# iF11L.net
KiCad netlist of a schematic drawn in Altium Designer
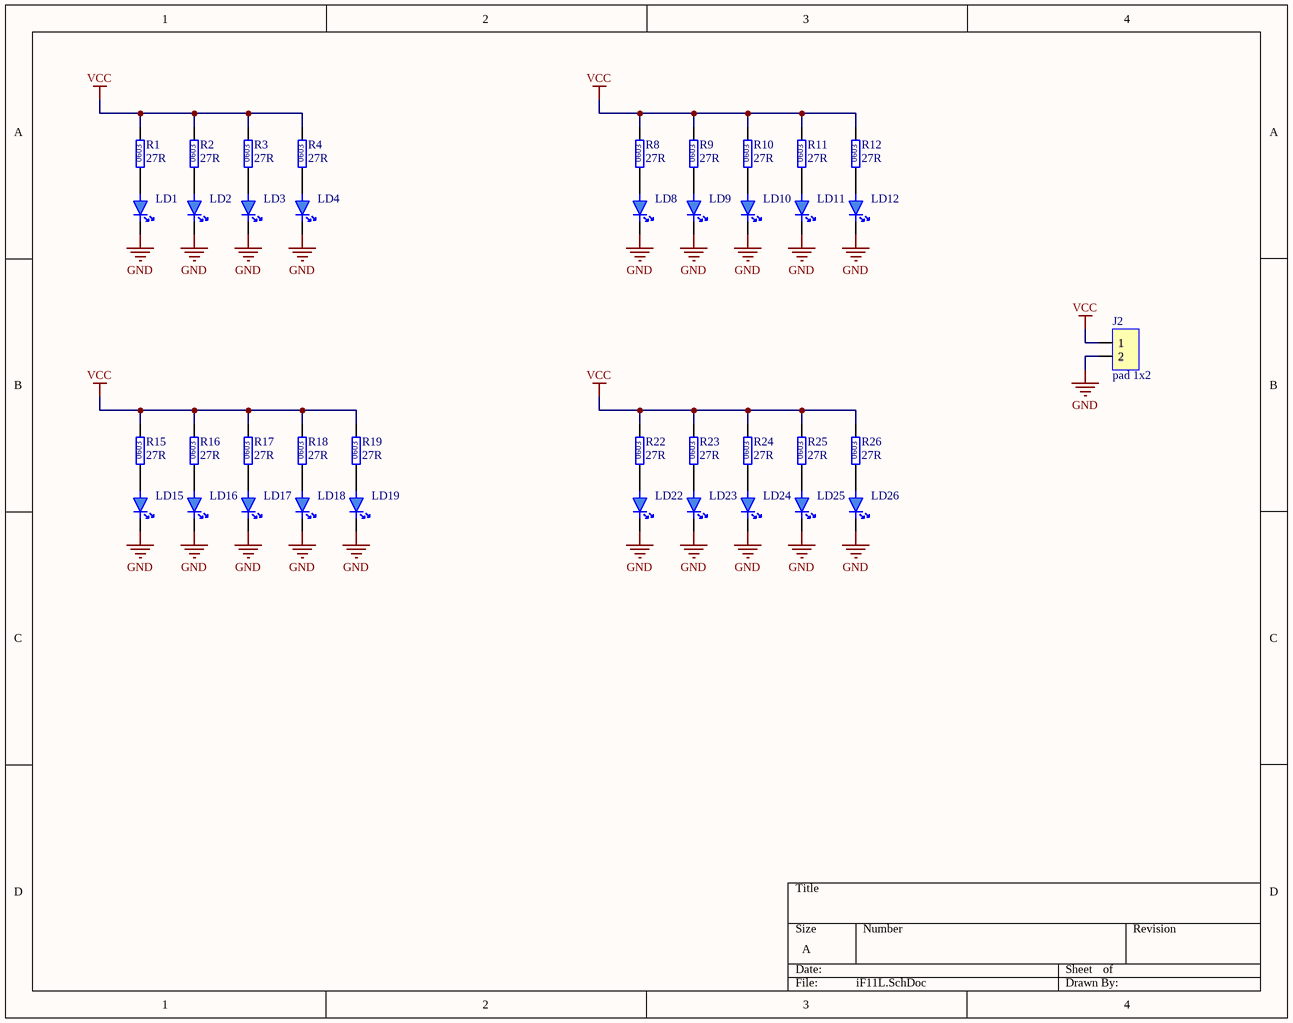
[diagram p0: iF11L.SchDoc]

(export (version "E")
  (design (tool "Eeschema 10.0.6"))
  (components
    (comp (ref "J2")
      (value "pad 1x2")
      (footprint "Pad-1x2")
      (description "2 Pin SMD Pad")
      (libsource (lib "Connector") (part "Pad-1x2"))
    )
    (comp (ref "LD1")
      (value "HQ19-2101UWCE2 0603")
      (footprint "LED-0603-WS")
      (libsource (lib "Optoelectronics") (part "LED WS"))
    )
    (comp (ref "LD2")
      (value "HQ19-2101UWCE2 0603")
      (footprint "LED-0603-WS")
      (libsource (lib "Optoelectronics") (part "LED WS"))
    )
    (comp (ref "LD3")
      (value "HQ19-2101UWCE2 0603")
      (footprint "LED-0603-WS")
      (libsource (lib "Optoelectronics") (part "LED WS"))
    )
    (comp (ref "LD4")
      (value "HQ19-2101UWCE2 0603")
      (footprint "LED-0603-WS")
      (libsource (lib "Optoelectronics") (part "LED WS"))
    )
    (comp (ref "LD8")
      (value "HQ19-2101UWCE2 0603")
      (footprint "LED-0603-WS")
      (libsource (lib "Optoelectronics") (part "LED WS"))
    )
    (comp (ref "LD9")
      (value "HQ19-2101UWCE2 0603")
      (footprint "LED-0603-WS")
      (libsource (lib "Optoelectronics") (part "LED WS"))
    )
    (comp (ref "LD10")
      (value "HQ19-2101UWCE2 0603")
      (footprint "LED-0603-WS")
      (libsource (lib "Optoelectronics") (part "LED WS"))
    )
    (comp (ref "LD11")
      (value "HQ19-2101UWCE2 0603")
      (footprint "LED-0603-WS")
      (libsource (lib "Optoelectronics") (part "LED WS"))
    )
    (comp (ref "LD12")
      (value "HQ19-2101UWCE2 0603")
      (footprint "LED-0603-WS")
      (libsource (lib "Optoelectronics") (part "LED WS"))
    )
    (comp (ref "LD15")
      (value "HQ19-2101UWCE2 0603")
      (footprint "LED-0603-WS")
      (libsource (lib "Optoelectronics") (part "LED WS"))
    )
    (comp (ref "LD16")
      (value "HQ19-2101UWCE2 0603")
      (footprint "LED-0603-WS")
      (libsource (lib "Optoelectronics") (part "LED WS"))
    )
    (comp (ref "LD17")
      (value "HQ19-2101UWCE2 0603")
      (footprint "LED-0603-WS")
      (libsource (lib "Optoelectronics") (part "LED WS"))
    )
    (comp (ref "LD18")
      (value "HQ19-2101UWCE2 0603")
      (footprint "LED-0603-WS")
      (libsource (lib "Optoelectronics") (part "LED WS"))
    )
    (comp (ref "LD19")
      (value "HQ19-2101UWCE2 0603")
      (footprint "LED-0603-WS")
      (libsource (lib "Optoelectronics") (part "LED WS"))
    )
    (comp (ref "LD22")
      (value "HQ19-2101UWCE2 0603")
      (footprint "LED-0603-WS")
      (libsource (lib "Optoelectronics") (part "LED WS"))
    )
    (comp (ref "LD23")
      (value "HQ19-2101UWCE2 0603")
      (footprint "LED-0603-WS")
      (libsource (lib "Optoelectronics") (part "LED WS"))
    )
    (comp (ref "LD24")
      (value "HQ19-2101UWCE2 0603")
      (footprint "LED-0603-WS")
      (libsource (lib "Optoelectronics") (part "LED WS"))
    )
    (comp (ref "LD25")
      (value "HQ19-2101UWCE2 0603")
      (footprint "LED-0603-WS")
      (libsource (lib "Optoelectronics") (part "LED WS"))
    )
    (comp (ref "LD26")
      (value "HQ19-2101UWCE2 0603")
      (footprint "LED-0603-WS")
      (libsource (lib "Optoelectronics") (part "LED WS"))
    )
    (comp (ref "R1")
      (value "27R")
      (footprint "R0603-LD")
      (description "5%")
      (fields (field (name "PART NO") "W-T-RE-RS03K270JT") (field (name "MANUFACTURER") "LAGEO"))
      (libsource (lib "Rescap") (part "R 0603 27R"))
    )
    (comp (ref "R2")
      (value "27R")
      (footprint "R0603-LD")
      (description "5%")
      (fields (field (name "PART NO") "W-T-RE-RS03K270JT") (field (name "MANUFACTURER") "LAGEO"))
      (libsource (lib "Rescap") (part "R 0603 27R"))
    )
    (comp (ref "R3")
      (value "27R")
      (footprint "R0603-LD")
      (description "5%")
      (fields (field (name "PART NO") "W-T-RE-RS03K270JT") (field (name "MANUFACTURER") "LAGEO"))
      (libsource (lib "Rescap") (part "R 0603 27R"))
    )
    (comp (ref "R4")
      (value "27R")
      (footprint "R0603-LD")
      (description "5%")
      (fields (field (name "PART NO") "W-T-RE-RS03K270JT") (field (name "MANUFACTURER") "LAGEO"))
      (libsource (lib "Rescap") (part "R 0603 27R"))
    )
    (comp (ref "R8")
      (value "27R")
      (footprint "R0603-LD")
      (description "5%")
      (fields (field (name "PART NO") "W-T-RE-RS03K270JT") (field (name "MANUFACTURER") "LAGEO"))
      (libsource (lib "Rescap") (part "R 0603 27R"))
    )
    (comp (ref "R9")
      (value "27R")
      (footprint "R0603-LD")
      (description "5%")
      (fields (field (name "PART NO") "W-T-RE-RS03K270JT") (field (name "MANUFACTURER") "LAGEO"))
      (libsource (lib "Rescap") (part "R 0603 27R"))
    )
    (comp (ref "R10")
      (value "27R")
      (footprint "R0603-LD")
      (description "5%")
      (fields (field (name "PART NO") "W-T-RE-RS03K270JT") (field (name "MANUFACTURER") "LAGEO"))
      (libsource (lib "Rescap") (part "R 0603 27R"))
    )
    (comp (ref "R11")
      (value "27R")
      (footprint "R0603-LD")
      (description "5%")
      (fields (field (name "PART NO") "W-T-RE-RS03K270JT") (field (name "MANUFACTURER") "LAGEO"))
      (libsource (lib "Rescap") (part "R 0603 27R"))
    )
    (comp (ref "R12")
      (value "27R")
      (footprint "R0603-LD")
      (description "5%")
      (fields (field (name "PART NO") "W-T-RE-RS03K270JT") (field (name "MANUFACTURER") "LAGEO"))
      (libsource (lib "Rescap") (part "R 0603 27R"))
    )
    (comp (ref "R15")
      (value "27R")
      (footprint "R0603-LD")
      (description "5%")
      (fields (field (name "PART NO") "W-T-RE-RS03K270JT") (field (name "MANUFACTURER") "LAGEO"))
      (libsource (lib "Rescap") (part "R 0603 27R"))
    )
    (comp (ref "R16")
      (value "27R")
      (footprint "R0603-LD")
      (description "5%")
      (fields (field (name "PART NO") "W-T-RE-RS03K270JT") (field (name "MANUFACTURER") "LAGEO"))
      (libsource (lib "Rescap") (part "R 0603 27R"))
    )
    (comp (ref "R17")
      (value "27R")
      (footprint "R0603-LD")
      (description "5%")
      (fields (field (name "PART NO") "W-T-RE-RS03K270JT") (field (name "MANUFACTURER") "LAGEO"))
      (libsource (lib "Rescap") (part "R 0603 27R"))
    )
    (comp (ref "R18")
      (value "27R")
      (footprint "R0603-LD")
      (description "5%")
      (fields (field (name "PART NO") "W-T-RE-RS03K270JT") (field (name "MANUFACTURER") "LAGEO"))
      (libsource (lib "Rescap") (part "R 0603 27R"))
    )
    (comp (ref "R19")
      (value "27R")
      (footprint "R0603-LD")
      (description "5%")
      (fields (field (name "PART NO") "W-T-RE-RS03K270JT") (field (name "MANUFACTURER") "LAGEO"))
      (libsource (lib "Rescap") (part "R 0603 27R"))
    )
    (comp (ref "R22")
      (value "27R")
      (footprint "R0603-LD")
      (description "5%")
      (fields (field (name "PART NO") "W-T-RE-RS03K270JT") (field (name "MANUFACTURER") "LAGEO"))
      (libsource (lib "Rescap") (part "R 0603 27R"))
    )
    (comp (ref "R23")
      (value "27R")
      (footprint "R0603-LD")
      (description "5%")
      (fields (field (name "PART NO") "W-T-RE-RS03K270JT") (field (name "MANUFACTURER") "LAGEO"))
      (libsource (lib "Rescap") (part "R 0603 27R"))
    )
    (comp (ref "R24")
      (value "27R")
      (footprint "R0603-LD")
      (description "5%")
      (fields (field (name "PART NO") "W-T-RE-RS03K270JT") (field (name "MANUFACTURER") "LAGEO"))
      (libsource (lib "Rescap") (part "R 0603 27R"))
    )
    (comp (ref "R25")
      (value "27R")
      (footprint "R0603-LD")
      (description "5%")
      (fields (field (name "PART NO") "W-T-RE-RS03K270JT") (field (name "MANUFACTURER") "LAGEO"))
      (libsource (lib "Rescap") (part "R 0603 27R"))
    )
    (comp (ref "R26")
      (value "27R")
      (footprint "R0603-LD")
      (description "5%")
      (fields (field (name "PART NO") "W-T-RE-RS03K270JT") (field (name "MANUFACTURER") "LAGEO"))
      (libsource (lib "Rescap") (part "R 0603 27R"))
    )
  )
  (nets
    (net (code "1") (name "GND") (class "Default")
      (node (ref "J2") (pin "2") (pinfunction "2_2") (pintype "passive"))
      (node (ref "LD1") (pin "2") (pinfunction "K_2") (pintype "passive"))
      (node (ref "LD10") (pin "2") (pinfunction "K_2") (pintype "passive"))
      (node (ref "LD11") (pin "2") (pinfunction "K_2") (pintype "passive"))
      (node (ref "LD12") (pin "2") (pinfunction "K_2") (pintype "passive"))
      (node (ref "LD15") (pin "2") (pinfunction "K_2") (pintype "passive"))
      (node (ref "LD16") (pin "2") (pinfunction "K_2") (pintype "passive"))
      (node (ref "LD17") (pin "2") (pinfunction "K_2") (pintype "passive"))
      (node (ref "LD18") (pin "2") (pinfunction "K_2") (pintype "passive"))
      (node (ref "LD19") (pin "2") (pinfunction "K_2") (pintype "passive"))
      (node (ref "LD2") (pin "2") (pinfunction "K_2") (pintype "passive"))
      (node (ref "LD22") (pin "2") (pinfunction "K_2") (pintype "passive"))
      (node (ref "LD23") (pin "2") (pinfunction "K_2") (pintype "passive"))
      (node (ref "LD24") (pin "2") (pinfunction "K_2") (pintype "passive"))
      (node (ref "LD25") (pin "2") (pinfunction "K_2") (pintype "passive"))
      (node (ref "LD26") (pin "2") (pinfunction "K_2") (pintype "passive"))
      (node (ref "LD3") (pin "2") (pinfunction "K_2") (pintype "passive"))
      (node (ref "LD4") (pin "2") (pinfunction "K_2") (pintype "passive"))
      (node (ref "LD8") (pin "2") (pinfunction "K_2") (pintype "passive"))
      (node (ref "LD9") (pin "2") (pinfunction "K_2") (pintype "passive"))
    )
    (net (code "2") (name "Net-(LD1-A)") (class "Default")
      (node (ref "LD1") (pin "1") (pinfunction "A_1") (pintype "passive"))
      (node (ref "R1") (pin "1") (pinfunction "1_1") (pintype "passive"))
    )
    (net (code "3") (name "Net-(LD2-A)") (class "Default")
      (node (ref "LD2") (pin "1") (pinfunction "A_1") (pintype "passive"))
      (node (ref "R2") (pin "1") (pinfunction "1_1") (pintype "passive"))
    )
    (net (code "4") (name "Net-(LD3-A)") (class "Default")
      (node (ref "LD3") (pin "1") (pinfunction "A_1") (pintype "passive"))
      (node (ref "R3") (pin "1") (pinfunction "1_1") (pintype "passive"))
    )
    (net (code "5") (name "Net-(LD4-A)") (class "Default")
      (node (ref "LD4") (pin "1") (pinfunction "A_1") (pintype "passive"))
      (node (ref "R4") (pin "1") (pinfunction "1_1") (pintype "passive"))
    )
    (net (code "6") (name "Net-(LD8-A)") (class "Default")
      (node (ref "LD8") (pin "1") (pinfunction "A_1") (pintype "passive"))
      (node (ref "R8") (pin "1") (pinfunction "1_1") (pintype "passive"))
    )
    (net (code "7") (name "Net-(LD9-A)") (class "Default")
      (node (ref "LD9") (pin "1") (pinfunction "A_1") (pintype "passive"))
      (node (ref "R9") (pin "1") (pinfunction "1_1") (pintype "passive"))
    )
    (net (code "8") (name "Net-(LD10-A)") (class "Default")
      (node (ref "LD10") (pin "1") (pinfunction "A_1") (pintype "passive"))
      (node (ref "R10") (pin "1") (pinfunction "1_1") (pintype "passive"))
    )
    (net (code "9") (name "Net-(LD11-A)") (class "Default")
      (node (ref "LD11") (pin "1") (pinfunction "A_1") (pintype "passive"))
      (node (ref "R11") (pin "1") (pinfunction "1_1") (pintype "passive"))
    )
    (net (code "10") (name "Net-(LD12-A)") (class "Default")
      (node (ref "LD12") (pin "1") (pinfunction "A_1") (pintype "passive"))
      (node (ref "R12") (pin "1") (pinfunction "1_1") (pintype "passive"))
    )
    (net (code "11") (name "Net-(LD15-A)") (class "Default")
      (node (ref "LD15") (pin "1") (pinfunction "A_1") (pintype "passive"))
      (node (ref "R15") (pin "1") (pinfunction "1_1") (pintype "passive"))
    )
    (net (code "12") (name "Net-(LD16-A)") (class "Default")
      (node (ref "LD16") (pin "1") (pinfunction "A_1") (pintype "passive"))
      (node (ref "R16") (pin "1") (pinfunction "1_1") (pintype "passive"))
    )
    (net (code "13") (name "Net-(LD17-A)") (class "Default")
      (node (ref "LD17") (pin "1") (pinfunction "A_1") (pintype "passive"))
      (node (ref "R17") (pin "1") (pinfunction "1_1") (pintype "passive"))
    )
    (net (code "14") (name "Net-(LD18-A)") (class "Default")
      (node (ref "LD18") (pin "1") (pinfunction "A_1") (pintype "passive"))
      (node (ref "R18") (pin "1") (pinfunction "1_1") (pintype "passive"))
    )
    (net (code "15") (name "Net-(LD19-A)") (class "Default")
      (node (ref "LD19") (pin "1") (pinfunction "A_1") (pintype "passive"))
      (node (ref "R19") (pin "1") (pinfunction "1_1") (pintype "passive"))
    )
    (net (code "16") (name "Net-(LD22-A)") (class "Default")
      (node (ref "LD22") (pin "1") (pinfunction "A_1") (pintype "passive"))
      (node (ref "R22") (pin "1") (pinfunction "1_1") (pintype "passive"))
    )
    (net (code "17") (name "Net-(LD23-A)") (class "Default")
      (node (ref "LD23") (pin "1") (pinfunction "A_1") (pintype "passive"))
      (node (ref "R23") (pin "1") (pinfunction "1_1") (pintype "passive"))
    )
    (net (code "18") (name "Net-(LD24-A)") (class "Default")
      (node (ref "LD24") (pin "1") (pinfunction "A_1") (pintype "passive"))
      (node (ref "R24") (pin "1") (pinfunction "1_1") (pintype "passive"))
    )
    (net (code "19") (name "Net-(LD25-A)") (class "Default")
      (node (ref "LD25") (pin "1") (pinfunction "A_1") (pintype "passive"))
      (node (ref "R25") (pin "1") (pinfunction "1_1") (pintype "passive"))
    )
    (net (code "20") (name "Net-(LD26-A)") (class "Default")
      (node (ref "LD26") (pin "1") (pinfunction "A_1") (pintype "passive"))
      (node (ref "R26") (pin "1") (pinfunction "1_1") (pintype "passive"))
    )
    (net (code "21") (name "VCC") (class "Default")
      (node (ref "J2") (pin "1") (pinfunction "1_1") (pintype "passive"))
      (node (ref "R1") (pin "2") (pinfunction "2_2") (pintype "passive"))
      (node (ref "R10") (pin "2") (pinfunction "2_2") (pintype "passive"))
      (node (ref "R11") (pin "2") (pinfunction "2_2") (pintype "passive"))
      (node (ref "R12") (pin "2") (pinfunction "2_2") (pintype "passive"))
      (node (ref "R15") (pin "2") (pinfunction "2_2") (pintype "passive"))
      (node (ref "R16") (pin "2") (pinfunction "2_2") (pintype "passive"))
      (node (ref "R17") (pin "2") (pinfunction "2_2") (pintype "passive"))
      (node (ref "R18") (pin "2") (pinfunction "2_2") (pintype "passive"))
      (node (ref "R19") (pin "2") (pinfunction "2_2") (pintype "passive"))
      (node (ref "R2") (pin "2") (pinfunction "2_2") (pintype "passive"))
      (node (ref "R22") (pin "2") (pinfunction "2_2") (pintype "passive"))
      (node (ref "R23") (pin "2") (pinfunction "2_2") (pintype "passive"))
      (node (ref "R24") (pin "2") (pinfunction "2_2") (pintype "passive"))
      (node (ref "R25") (pin "2") (pinfunction "2_2") (pintype "passive"))
      (node (ref "R26") (pin "2") (pinfunction "2_2") (pintype "passive"))
      (node (ref "R3") (pin "2") (pinfunction "2_2") (pintype "passive"))
      (node (ref "R4") (pin "2") (pinfunction "2_2") (pintype "passive"))
      (node (ref "R8") (pin "2") (pinfunction "2_2") (pintype "passive"))
      (node (ref "R9") (pin "2") (pinfunction "2_2") (pintype "passive"))
    )
  )
)
